# PWM_LuefterReglerGT15V.net
KiCad netlist of a schematic drawn in EAGLE
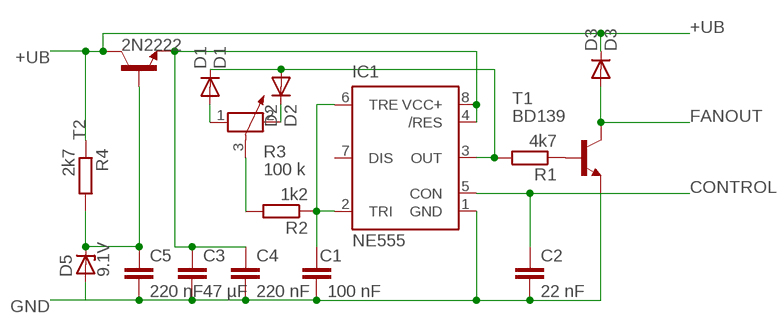
[diagram p0: schematic, sheet 1]

(export (version "E")
  (design (tool "Eeschema 10.0.6"))
  (components
    (comp (ref "C1")
      (value "100 nF")
      (footprint "eagle-import:C2.5-3")
      (libsource (lib "eagle-import") (part "C2,5-3"))
    )
    (comp (ref "C2")
      (value "22 nF")
      (footprint "eagle-import:C7.5B3")
      (libsource (lib "eagle-import") (part "C7.5/3"))
    )
    (comp (ref "C3")
      (value "47 µF")
      (footprint "eagle-import:C5B4.5")
      (libsource (lib "eagle-import") (part "C5/4.5"))
    )
    (comp (ref "C4")
      (value "220 nF")
      (footprint "eagle-import:C7.5B3")
      (libsource (lib "eagle-import") (part "C7.5/3"))
    )
    (comp (ref "C5")
      (value "220 nF")
      (footprint "eagle-import:C7.5B3")
      (libsource (lib "eagle-import") (part "C7.5/3"))
    )
    (comp (ref "D1")
      (value "D1")
      (footprint "eagle-import:DO35-10")
      (libsource (lib "eagle-import") (part "1N4148DO35-10"))
    )
    (comp (ref "D2")
      (value "D2")
      (footprint "eagle-import:DO35-10")
      (libsource (lib "eagle-import") (part "1N4148DO35-10"))
    )
    (comp (ref "D3")
      (value "D3")
      (footprint "eagle-import:DO35-10")
      (libsource (lib "eagle-import") (part "1N4148DO35-10"))
    )
    (comp (ref "D5")
      (value "9.1V")
      (footprint "eagle-import:ZDIO-7.5")
      (libsource (lib "eagle-import") (part "ZENER-DIODEZD-7.5"))
    )
    (comp (ref "IC1")
      (value "NE555")
      (footprint "eagle-import:DIL-08")
      (fields (field (name "MF") "Arrow Electronics") (field (name "MPN") "NE555N"))
      (libsource (lib "eagle-import") (part "NE555"))
    )
    (comp (ref "R1")
      (value "4k7")
      (footprint "eagle-import:0207_10")
      (libsource (lib "eagle-import") (part "R-EU_0207/10"))
    )
    (comp (ref "R2")
      (value "1k2")
      (footprint "eagle-import:0207_10")
      (libsource (lib "eagle-import") (part "R-EU_0207/10"))
    )
    (comp (ref "R3")
      (value "100 k")
      (footprint "eagle-import:PT-10")
      (libsource (lib "eagle-import") (part "POTENTIOMETER_PT-10"))
    )
    (comp (ref "R4")
      (value "2k7")
      (footprint "eagle-import:0207_10")
      (libsource (lib "eagle-import") (part "R-EU_0207/10"))
    )
    (comp (ref "T1")
      (value "BD139")
      (footprint "eagle-import:TO126")
      (libsource (lib "eagle-import") (part "BD139"))
    )
    (comp (ref "T2")
      (value "2N2222")
      (footprint "eagle-import:TO18")
      (libsource (lib "eagle-import") (part "2N2222"))
    )
  )
  (nets
    (net (code "1") (name "/+UB") (class "Default")
      (node (ref "D3") (pin "C") (pinfunction "C_C") (pintype "passive"))
      (node (ref "R4") (pin "1") (pinfunction "1_1") (pintype "passive"))
      (node (ref "T2") (pin "3") (pinfunction "C_3") (pintype "passive"))
    )
    (net (code "2") (name "/CONTROL") (class "Default")
      (node (ref "C2") (pin "2") (pinfunction "2_2") (pintype "passive"))
      (node (ref "IC1") (pin "5") (pinfunction "CON_5") (pintype "input"))
    )
    (net (code "3") (name "/FANOUT") (class "Default")
      (node (ref "D3") (pin "A") (pinfunction "A_A") (pintype "passive"))
      (node (ref "T1") (pin "2") (pinfunction "C_2") (pintype "passive"))
    )
    (net (code "4") (name "/GND") (class "Default")
      (node (ref "C1") (pin "1") (pinfunction "1_1") (pintype "passive"))
      (node (ref "C2") (pin "1") (pinfunction "1_1") (pintype "passive"))
      (node (ref "C3") (pin "2") (pinfunction "2_2") (pintype "passive"))
      (node (ref "C4") (pin "2") (pinfunction "2_2") (pintype "passive"))
      (node (ref "C5") (pin "2") (pinfunction "2_2") (pintype "passive"))
      (node (ref "D5") (pin "A") (pinfunction "A_A") (pintype "passive"))
      (node (ref "IC1") (pin "1") (pinfunction "GND_1") (pintype "power_in"))
      (node (ref "T1") (pin "1") (pinfunction "E_1") (pintype "passive"))
    )
    (net (code "5") (name "Net-(D1-PadA)") (class "Default")
      (node (ref "D1") (pin "A") (pinfunction "A_A") (pintype "passive"))
      (node (ref "R3") (pin "1") (pinfunction "1_1") (pintype "passive"))
    )
    (net (code "6") (name "Net-(D2-PadC)") (class "Default")
      (node (ref "D2") (pin "C") (pinfunction "C_C") (pintype "passive"))
      (node (ref "R3") (pin "2") (pinfunction "2_2") (pintype "passive"))
    )
    (net (code "7") (name "Net-(IC1-OUT)") (class "Default")
      (node (ref "D1") (pin "C") (pinfunction "C_C") (pintype "passive"))
      (node (ref "D2") (pin "A") (pinfunction "A_A") (pintype "passive"))
      (node (ref "IC1") (pin "3") (pinfunction "OUT_3") (pintype "output"))
      (node (ref "R1") (pin "2") (pinfunction "2_2") (pintype "passive"))
    )
    (net (code "8") (name "Net-(IC1-TRE)") (class "Default")
      (node (ref "C1") (pin "2") (pinfunction "2_2") (pintype "passive"))
      (node (ref "IC1") (pin "2") (pinfunction "TRI_2") (pintype "input"))
      (node (ref "IC1") (pin "6") (pinfunction "TRE_6") (pintype "input"))
      (node (ref "R2") (pin "1") (pinfunction "1_1") (pintype "passive"))
    )
    (net (code "9") (name "Net-(IC1-VCC+)") (class "Default")
      (node (ref "C3") (pin "1") (pinfunction "1_1") (pintype "passive"))
      (node (ref "C4") (pin "1") (pinfunction "1_1") (pintype "passive"))
      (node (ref "IC1") (pin "4") (pinfunction "/RES_4") (pintype "input"))
      (node (ref "IC1") (pin "8") (pinfunction "VCC+_8") (pintype "power_in"))
      (node (ref "T2") (pin "1") (pinfunction "E_1") (pintype "passive"))
    )
    (net (code "10") (name "Net-(R2-Pad2)") (class "Default")
      (node (ref "R2") (pin "2") (pinfunction "2_2") (pintype "passive"))
      (node (ref "R3") (pin "3") (pinfunction "3_3") (pintype "passive"))
    )
    (net (code "11") (name "Net-(T1-B)") (class "Default")
      (node (ref "R1") (pin "1") (pinfunction "1_1") (pintype "passive"))
      (node (ref "T1") (pin "3") (pinfunction "B_3") (pintype "passive"))
    )
    (net (code "12") (name "Net-(T2-B)") (class "Default")
      (node (ref "C5") (pin "1") (pinfunction "1_1") (pintype "passive"))
      (node (ref "D5") (pin "C") (pinfunction "C_C") (pintype "passive"))
      (node (ref "R4") (pin "2") (pinfunction "2_2") (pintype "passive"))
      (node (ref "T2") (pin "2") (pinfunction "B_2") (pintype "passive"))
    )
    (net (code "13") (name "unconnected-(IC1-DIS-Pad7)") (class "Default")
      (node (ref "IC1") (pin "7") (pinfunction "DIS_7") (pintype "input"))
    )
  )
)
